# ad2_1.net
KiCad netlist of a schematic drawn in Altium Designer
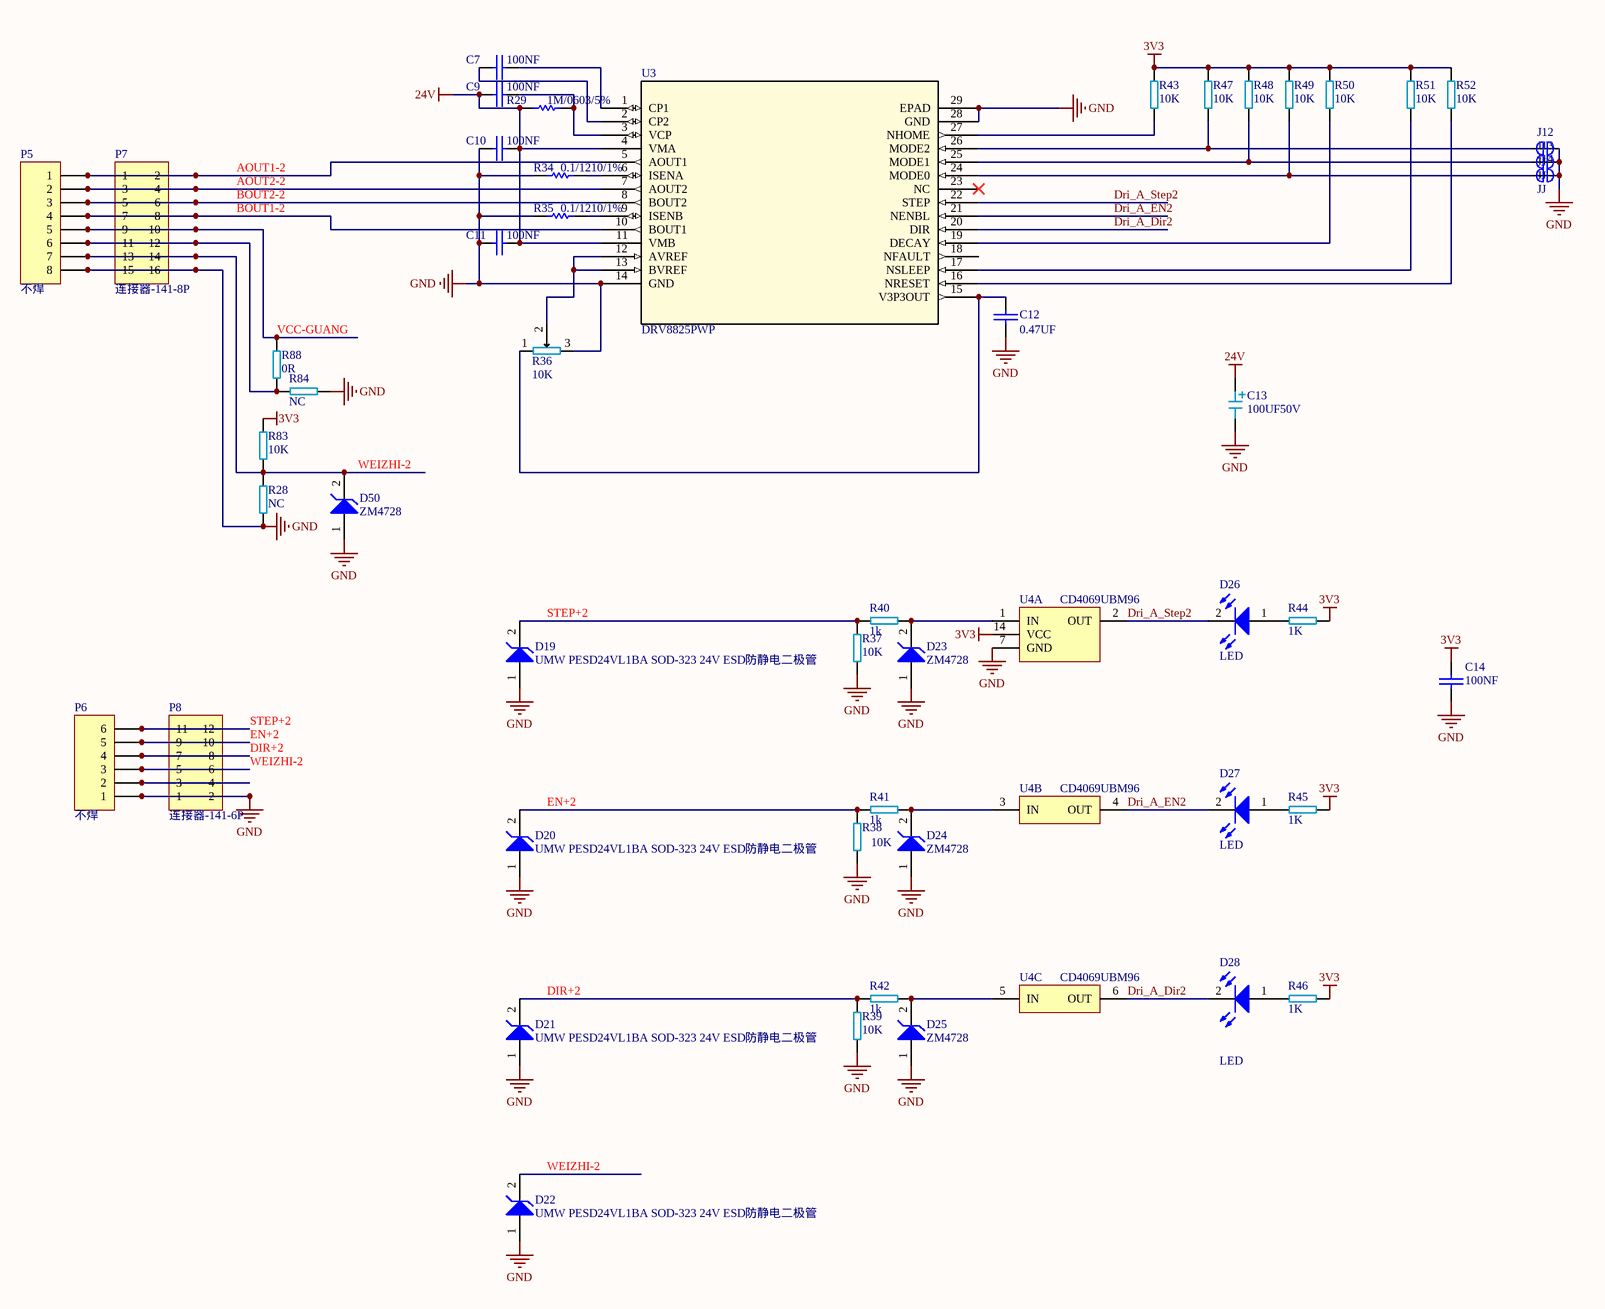
[diagram p0: ad2_1.schdoc]

(export (version "E")
  (design (tool "Eeschema 10.0.6"))
  (components
    (comp (ref "C7")
      (value "100NF")
      (footprint "C0603")
      (description "Capacitor")
      (libsource (lib "Miscellaneous Devices") (part "CAP"))
    )
    (comp (ref "C9")
      (value "100NF")
      (footprint "C0603")
      (description "Capacitor")
      (libsource (lib "Miscellaneous Devices") (part "CAP"))
    )
    (comp (ref "C10")
      (value "100NF")
      (footprint "C0603")
      (description "Capacitor")
      (libsource (lib "Miscellaneous Devices") (part "CAP"))
    )
    (comp (ref "C11")
      (value "100NF")
      (footprint "C0603")
      (description "Capacitor")
      (libsource (lib "Miscellaneous Devices") (part "CAP"))
    )
    (comp (ref "C12")
      (value "0.47UF")
      (footprint "C0603")
      (description "Capacitor")
      (libsource (lib "Miscellaneous Devices") (part "CAP"))
    )
    (comp (ref "C13")
      (value "100UF50V")
      (footprint "CE8")
      (description "铝电解电容")
      (libsource (lib "base") (part "C+"))
    )
    (comp (ref "C14")
      (value "100NF")
      (footprint "C0603")
      (description "Capacitor")
      (libsource (lib "Miscellaneous Devices") (part "CAP"))
    )
    (comp (ref "D19")
      (value "UMW PESD24VL1BA SOD-323 24V ESD防静电二极管")
      (footprint "SOD323")
      (description "稳压管")
      (fields (field (name "PUBLISHER") "Altium Limited"))
      (libsource (lib "base") (part "TVS-SMA"))
    )
    (comp (ref "D20")
      (value "UMW PESD24VL1BA SOD-323 24V ESD防静电二极管")
      (footprint "SOD323")
      (description "稳压管")
      (fields (field (name "PUBLISHER") "Altium Limited"))
      (libsource (lib "base") (part "TVS-SMA"))
    )
    (comp (ref "D21")
      (value "UMW PESD24VL1BA SOD-323 24V ESD防静电二极管")
      (footprint "SOD323")
      (description "稳压管")
      (fields (field (name "PUBLISHER") "Altium Limited"))
      (libsource (lib "base") (part "TVS-SMA"))
    )
    (comp (ref "D22")
      (value "UMW PESD24VL1BA SOD-323 24V ESD防静电二极管")
      (footprint "SOD323")
      (description "稳压管")
      (fields (field (name "PUBLISHER") "Altium Limited"))
      (libsource (lib "base") (part "TVS-SMA"))
    )
    (comp (ref "D23")
      (value "ZM4728")
      (footprint "D1206")
      (description "稳压管")
      (fields (field (name "PUBLISHER") "Altium Limited"))
      (libsource (lib "base") (part "TVS-SMA"))
    )
    (comp (ref "D24")
      (value "ZM4728")
      (footprint "D1206")
      (description "稳压管")
      (fields (field (name "PUBLISHER") "Altium Limited"))
      (libsource (lib "base") (part "TVS-SMA"))
    )
    (comp (ref "D25")
      (value "ZM4728")
      (footprint "D1206")
      (description "稳压管")
      (fields (field (name "PUBLISHER") "Altium Limited"))
      (libsource (lib "base") (part "TVS-SMA"))
    )
    (comp (ref "D26")
      (value "LED")
      (footprint "LED0603")
      (description "LED0603")
      (fields (field (name "PUBLISHER") "Altium Limited"))
      (libsource (lib "base") (part "LED0603"))
    )
    (comp (ref "D27")
      (value "LED")
      (footprint "LED0603")
      (description "LED0603")
      (fields (field (name "PUBLISHER") "Altium Limited"))
      (libsource (lib "base") (part "LED0603"))
    )
    (comp (ref "D28")
      (value "LED")
      (footprint "LED0603")
      (description "LED0603")
      (fields (field (name "PUBLISHER") "Altium Limited"))
      (libsource (lib "base") (part "LED0603"))
    )
    (comp (ref "D50")
      (value "ZM4728")
      (footprint "D1206")
      (description "稳压管")
      (fields (field (name "PUBLISHER") "Altium Limited"))
      (libsource (lib "base") (part "TVS-SMA"))
    )
    (comp (ref "J12")
      (value "JJ")
      (footprint "TIAOXIAN-PAN")
      (description "跳线")
      (libsource (lib "base") (part "JJ"))
    )
    (comp (ref "J13")
      (value "JJ")
      (footprint "TIAOXIAN-PAN")
      (description "跳线")
      (libsource (lib "base") (part "JJ"))
    )
    (comp (ref "J14")
      (value "JJ")
      (footprint "TIAOXIAN-PAN")
      (description "跳线")
      (libsource (lib "base") (part "JJ"))
    )
    (comp (ref "P5")
      (value "不焊")
      (footprint "SIP8")
      (description "连接器")
      (fields (field (name "PUBLISHER") "Altium Limited"))
      (libsource (lib "base") (part "SIP8"))
    )
    (comp (ref "P6")
      (value "不焊")
      (footprint "SIP6")
      (description "连接器")
      (fields (field (name "PUBLISHER") "Altium Limited"))
      (libsource (lib "base") (part "SIP6"))
    )
    (comp (ref "P7")
      (value "连接器-141-8P")
      (footprint "141V-8P")
      (description "连接器")
      (fields (field (name "PUBLISHER") "Altium Limited"))
      (libsource (lib "base") (part "DIC16"))
    )
    (comp (ref "P8")
      (value "连接器-141-6P")
      (footprint "141V-6P")
      (description "连接器")
      (fields (field (name "PUBLISHER") "Altium Limited"))
      (libsource (lib "base") (part "DIC12"))
    )
    (comp (ref "R28")
      (value "NC")
      (footprint "R0603")
      (description "贴片电阻")
      (libsource (lib "base") (part "R-0603"))
    )
    (comp (ref "R29")
      (value "1M/0603/5%")
      (footprint "R0603")
      (description "Resistor")
      (fields (field (name "PUBLISHER") "Altium Limited"))
      (libsource (lib "Miscellaneous Devices") (part "Res1"))
    )
    (comp (ref "R34")
      (value "0.1/1210/1%")
      (footprint "R1210")
      (description "Resistor")
      (fields (field (name "PUBLISHER") "Altium Limited"))
      (libsource (lib "Miscellaneous Devices") (part "Res1"))
    )
    (comp (ref "R35")
      (value "0.1/1210/1%")
      (footprint "R1210")
      (description "Resistor")
      (fields (field (name "PUBLISHER") "Altium Limited"))
      (libsource (lib "Miscellaneous Devices") (part "Res1"))
    )
    (comp (ref "R36")
      (value "10K")
      (footprint "RR-MINI-SMD")
      (description "电位器")
      (libsource (lib "base") (part "RR"))
    )
    (comp (ref "R37")
      (value "10K")
      (footprint "R0603")
      (description "贴片电阻")
      (libsource (lib "base") (part "R-0603"))
    )
    (comp (ref "R38")
      (value "10K")
      (footprint "R0603")
      (description "贴片电阻")
      (libsource (lib "base") (part "R-0603"))
    )
    (comp (ref "R39")
      (value "10K")
      (footprint "R0603")
      (description "贴片电阻")
      (libsource (lib "base") (part "R-0603"))
    )
    (comp (ref "R40")
      (value "1k")
      (footprint "R0603")
      (description "贴片电阻")
      (libsource (lib "base") (part "R-0603"))
    )
    (comp (ref "R41")
      (value "1k")
      (footprint "R0603")
      (description "贴片电阻")
      (libsource (lib "base") (part "R-0603"))
    )
    (comp (ref "R42")
      (value "1k")
      (footprint "R0603")
      (description "贴片电阻")
      (libsource (lib "base") (part "R-0603"))
    )
    (comp (ref "R43")
      (value "10K")
      (footprint "R0603")
      (description "贴片电阻")
      (libsource (lib "base") (part "R-0603"))
    )
    (comp (ref "R44")
      (value "1K")
      (footprint "R0603")
      (description "贴片电阻")
      (libsource (lib "base") (part "R-0603"))
    )
    (comp (ref "R45")
      (value "1K")
      (footprint "R0603")
      (description "贴片电阻")
      (libsource (lib "base") (part "R-0603"))
    )
    (comp (ref "R46")
      (value "1K")
      (footprint "R0603")
      (description "贴片电阻")
      (libsource (lib "base") (part "R-0603"))
    )
    (comp (ref "R47")
      (value "10K")
      (footprint "R0603")
      (description "贴片电阻")
      (libsource (lib "base") (part "R-0603"))
    )
    (comp (ref "R48")
      (value "10K")
      (footprint "R0603")
      (description "贴片电阻")
      (libsource (lib "base") (part "R-0603"))
    )
    (comp (ref "R49")
      (value "10K")
      (footprint "R0603")
      (description "贴片电阻")
      (libsource (lib "base") (part "R-0603"))
    )
    (comp (ref "R50")
      (value "10K")
      (footprint "R0603")
      (description "贴片电阻")
      (libsource (lib "base") (part "R-0603"))
    )
    (comp (ref "R51")
      (value "10K")
      (footprint "R0603")
      (description "贴片电阻")
      (libsource (lib "base") (part "R-0603"))
    )
    (comp (ref "R52")
      (value "10K")
      (footprint "R0603")
      (description "贴片电阻")
      (libsource (lib "base") (part "R-0603"))
    )
    (comp (ref "R83")
      (value "10K")
      (footprint "R0603")
      (description "贴片电阻")
      (libsource (lib "base") (part "R-0603"))
    )
    (comp (ref "R84")
      (value "NC")
      (footprint "R0603")
      (description "贴片电阻")
      (libsource (lib "base") (part "R-0603"))
    )
    (comp (ref "R88")
      (value "0R")
      (footprint "R0603")
      (description "贴片电阻")
      (libsource (lib "base") (part "R-0603"))
    )
    (comp (ref "U3")
      (value "DRV8825PWP")
      (footprint "HTSSOP28")
      (description "芯片")
      (libsource (lib "User") (part "DRV8825PWP"))
    )
    (comp (ref "U4")
      (value "CD4069UBM96")
      (footprint "SO14")
      (description "芯片")
      (libsource (lib "Chip") (part "CD4069"))
    )
  )
  (nets
    (net (code "1") (name "/AOUT1-2") (class "Default")
      (node (ref "P5") (pin "1") (pinfunction "1_1") (pintype "passive"))
      (node (ref "P7") (pin "1") (pinfunction "1_1") (pintype "passive"))
      (node (ref "P7") (pin "2") (pinfunction "2_2") (pintype "passive"))
      (node (ref "U3") (pin "5") (pinfunction "AOUT1_5") (pintype "output"))
    )
    (net (code "2") (name "/AOUT2-2") (class "Default")
      (node (ref "P5") (pin "2") (pinfunction "2_2") (pintype "passive"))
      (node (ref "P7") (pin "3") (pinfunction "3_3") (pintype "passive"))
      (node (ref "P7") (pin "4") (pinfunction "4_4") (pintype "passive"))
      (node (ref "U3") (pin "7") (pinfunction "AOUT2_7") (pintype "output"))
    )
    (net (code "3") (name "/BOUT1-2") (class "Default")
      (node (ref "P5") (pin "4") (pinfunction "4_4") (pintype "passive"))
      (node (ref "P7") (pin "7") (pinfunction "7_7") (pintype "passive"))
      (node (ref "P7") (pin "8") (pinfunction "8_8") (pintype "passive"))
      (node (ref "U3") (pin "10") (pinfunction "BOUT1_10") (pintype "output"))
    )
    (net (code "4") (name "/BOUT2-2") (class "Default")
      (node (ref "P5") (pin "3") (pinfunction "3_3") (pintype "passive"))
      (node (ref "P7") (pin "5") (pinfunction "5_5") (pintype "passive"))
      (node (ref "P7") (pin "6") (pinfunction "6_6") (pintype "passive"))
      (node (ref "U3") (pin "8") (pinfunction "BOUT2_8") (pintype "output"))
    )
    (net (code "5") (name "/DIR+2") (class "Default")
      (node (ref "D21") (pin "2") (pinfunction "2_2") (pintype "passive"))
      (node (ref "P6") (pin "4") (pinfunction "4_4") (pintype "passive"))
      (node (ref "P8") (pin "7") (pinfunction "7_7") (pintype "passive"))
      (node (ref "P8") (pin "8") (pinfunction "8_8") (pintype "passive"))
      (node (ref "R39") (pin "2") (pinfunction "2_2") (pintype "passive"))
      (node (ref "R42") (pin "2") (pinfunction "2_2") (pintype "passive"))
    )
    (net (code "6") (name "/Dri_A_Dir2") (class "Default")
      (node (ref "D28") (pin "2") (pinfunction "K_2") (pintype "passive"))
      (node (ref "U3") (pin "20") (pinfunction "DIR_20") (pintype "input"))
      (node (ref "U4") (pin "6") (pinfunction "OUT_6") (pintype "passive"))
    )
    (net (code "7") (name "/Dri_A_EN2") (class "Default")
      (node (ref "D27") (pin "2") (pinfunction "K_2") (pintype "passive"))
      (node (ref "U3") (pin "21") (pinfunction "NENBL_21") (pintype "input"))
      (node (ref "U4") (pin "4") (pinfunction "OUT_4") (pintype "passive"))
    )
    (net (code "8") (name "/Dri_A_Step2") (class "Default")
      (node (ref "D26") (pin "2") (pinfunction "K_2") (pintype "passive"))
      (node (ref "U3") (pin "22") (pinfunction "STEP_22") (pintype "input"))
      (node (ref "U4") (pin "2") (pinfunction "OUT_2") (pintype "passive"))
    )
    (net (code "9") (name "/EN+2") (class "Default")
      (node (ref "D20") (pin "2") (pinfunction "2_2") (pintype "passive"))
      (node (ref "P6") (pin "5") (pinfunction "5_5") (pintype "passive"))
      (node (ref "P8") (pin "10") (pinfunction "10_10") (pintype "passive"))
      (node (ref "P8") (pin "9") (pinfunction "9_9") (pintype "passive"))
      (node (ref "R38") (pin "2") (pinfunction "2_2") (pintype "passive"))
      (node (ref "R41") (pin "2") (pinfunction "2_2") (pintype "passive"))
    )
    (net (code "10") (name "/STEP+2") (class "Default")
      (node (ref "D19") (pin "2") (pinfunction "2_2") (pintype "passive"))
      (node (ref "P6") (pin "6") (pinfunction "6_6") (pintype "passive"))
      (node (ref "P8") (pin "11") (pinfunction "11_11") (pintype "passive"))
      (node (ref "P8") (pin "12") (pinfunction "12_12") (pintype "passive"))
      (node (ref "R37") (pin "2") (pinfunction "2_2") (pintype "passive"))
      (node (ref "R40") (pin "2") (pinfunction "2_2") (pintype "passive"))
    )
    (net (code "11") (name "/VCC-GUANG") (class "Default")
      (node (ref "P5") (pin "5") (pinfunction "5_5") (pintype "passive"))
      (node (ref "P7") (pin "10") (pinfunction "10_10") (pintype "passive"))
      (node (ref "P7") (pin "9") (pinfunction "9_9") (pintype "passive"))
      (node (ref "R88") (pin "2") (pinfunction "2_2") (pintype "passive"))
    )
    (net (code "12") (name "/WEIZHI-2") (class "Default")
      (node (ref "D22") (pin "2") (pinfunction "2_2") (pintype "passive"))
      (node (ref "D50") (pin "2") (pinfunction "2_2") (pintype "passive"))
      (node (ref "P5") (pin "7") (pinfunction "7_7") (pintype "passive"))
      (node (ref "P6") (pin "3") (pinfunction "3_3") (pintype "passive"))
      (node (ref "P7") (pin "13") (pinfunction "13_13") (pintype "passive"))
      (node (ref "P7") (pin "14") (pinfunction "14_14") (pintype "passive"))
      (node (ref "P8") (pin "5") (pinfunction "5_5") (pintype "passive"))
      (node (ref "P8") (pin "6") (pinfunction "6_6") (pintype "passive"))
      (node (ref "R28") (pin "2") (pinfunction "2_2") (pintype "passive"))
      (node (ref "R83") (pin "1") (pinfunction "1_1") (pintype "passive"))
    )
    (net (code "13") (name "3V3") (class "Default")
      (node (ref "C14") (pin "2") (pinfunction "2_2") (pintype "passive"))
      (node (ref "R43") (pin "2") (pinfunction "2_2") (pintype "passive"))
      (node (ref "R44") (pin "2") (pinfunction "2_2") (pintype "passive"))
      (node (ref "R45") (pin "2") (pinfunction "2_2") (pintype "passive"))
      (node (ref "R46") (pin "2") (pinfunction "2_2") (pintype "passive"))
      (node (ref "R47") (pin "2") (pinfunction "2_2") (pintype "passive"))
      (node (ref "R48") (pin "2") (pinfunction "2_2") (pintype "passive"))
      (node (ref "R49") (pin "2") (pinfunction "2_2") (pintype "passive"))
      (node (ref "R50") (pin "2") (pinfunction "2_2") (pintype "passive"))
      (node (ref "R51") (pin "2") (pinfunction "2_2") (pintype "passive"))
      (node (ref "R52") (pin "2") (pinfunction "2_2") (pintype "passive"))
      (node (ref "R83") (pin "2") (pinfunction "2_2") (pintype "passive"))
      (node (ref "U4") (pin "14") (pinfunction "VCC_14") (pintype "passive"))
    )
    (net (code "14") (name "24V") (class "Default")
      (node (ref "C10") (pin "2") (pinfunction "2_2") (pintype "passive"))
      (node (ref "C11") (pin "2") (pinfunction "2_2") (pintype "passive"))
      (node (ref "C13") (pin "1") (pinfunction "1_1") (pintype "passive"))
      (node (ref "C9") (pin "1") (pinfunction "1_1") (pintype "passive"))
      (node (ref "R29") (pin "2") (pinfunction "2_2") (pintype "passive"))
      (node (ref "U3") (pin "11") (pinfunction "VMB_11") (pintype "power_in"))
      (node (ref "U3") (pin "4") (pinfunction "VMA_4") (pintype "power_in"))
    )
    (net (code "15") (name "GND") (class "Default")
      (node (ref "C10") (pin "1") (pinfunction "1_1") (pintype "passive"))
      (node (ref "C11") (pin "1") (pinfunction "1_1") (pintype "passive"))
      (node (ref "C12") (pin "1") (pinfunction "1_1") (pintype "passive"))
      (node (ref "C13") (pin "2") (pinfunction "2_2") (pintype "passive"))
      (node (ref "C14") (pin "1") (pinfunction "1_1") (pintype "passive"))
      (node (ref "D19") (pin "1") (pinfunction "1_1") (pintype "passive"))
      (node (ref "D20") (pin "1") (pinfunction "1_1") (pintype "passive"))
      (node (ref "D21") (pin "1") (pinfunction "1_1") (pintype "passive"))
      (node (ref "D22") (pin "1") (pinfunction "1_1") (pintype "passive"))
      (node (ref "D23") (pin "1") (pinfunction "1_1") (pintype "passive"))
      (node (ref "D24") (pin "1") (pinfunction "1_1") (pintype "passive"))
      (node (ref "D25") (pin "1") (pinfunction "1_1") (pintype "passive"))
      (node (ref "D50") (pin "1") (pinfunction "1_1") (pintype "passive"))
      (node (ref "J12") (pin "2") (pinfunction "2_2") (pintype "passive"))
      (node (ref "J13") (pin "2") (pinfunction "2_2") (pintype "passive"))
      (node (ref "J14") (pin "2") (pinfunction "2_2") (pintype "passive"))
      (node (ref "P5") (pin "8") (pinfunction "8_8") (pintype "passive"))
      (node (ref "P6") (pin "1") (pinfunction "1_1") (pintype "passive"))
      (node (ref "P7") (pin "15") (pinfunction "15_15") (pintype "passive"))
      (node (ref "P7") (pin "16") (pinfunction "16_16") (pintype "passive"))
      (node (ref "P8") (pin "1") (pinfunction "1_1") (pintype "passive"))
      (node (ref "P8") (pin "2") (pinfunction "2_2") (pintype "passive"))
      (node (ref "R28") (pin "1") (pinfunction "1_1") (pintype "passive"))
      (node (ref "R34") (pin "2") (pinfunction "2_2") (pintype "passive"))
      (node (ref "R35") (pin "2") (pinfunction "2_2") (pintype "passive"))
      (node (ref "R36") (pin "3") (pinfunction "3_3") (pintype "passive"))
      (node (ref "R37") (pin "1") (pinfunction "1_1") (pintype "passive"))
      (node (ref "R38") (pin "1") (pinfunction "1_1") (pintype "passive"))
      (node (ref "R39") (pin "1") (pinfunction "1_1") (pintype "passive"))
      (node (ref "R84") (pin "1") (pinfunction "1_1") (pintype "passive"))
      (node (ref "U3") (pin "14") (pinfunction "GND_14") (pintype "power_in"))
      (node (ref "U3") (pin "28") (pinfunction "GND_28") (pintype "power_in"))
      (node (ref "U3") (pin "29") (pinfunction "EPAD_29") (pintype "passive"))
      (node (ref "U4") (pin "7") (pinfunction "GND_7") (pintype "passive"))
    )
    (net (code "16") (name "Net-(D26-A)") (class "Default")
      (node (ref "D26") (pin "1") (pinfunction "A_1") (pintype "passive"))
      (node (ref "R44") (pin "1") (pinfunction "1_1") (pintype "passive"))
    )
    (net (code "17") (name "Net-(D27-A)") (class "Default")
      (node (ref "D27") (pin "1") (pinfunction "A_1") (pintype "passive"))
      (node (ref "R45") (pin "1") (pinfunction "1_1") (pintype "passive"))
    )
    (net (code "18") (name "Net-(D28-A)") (class "Default")
      (node (ref "D28") (pin "1") (pinfunction "A_1") (pintype "passive"))
      (node (ref "R46") (pin "1") (pinfunction "1_1") (pintype "passive"))
    )
    (net (code "19") (name "Net-(P5-Pad6)") (class "Default")
      (node (ref "P5") (pin "6") (pinfunction "6_6") (pintype "passive"))
      (node (ref "P7") (pin "11") (pinfunction "11_11") (pintype "passive"))
      (node (ref "P7") (pin "12") (pinfunction "12_12") (pintype "passive"))
      (node (ref "R84") (pin "2") (pinfunction "2_2") (pintype "passive"))
      (node (ref "R88") (pin "1") (pinfunction "1_1") (pintype "passive"))
    )
    (net (code "20") (name "Net-(P6-Pad2)") (class "Default")
      (node (ref "P6") (pin "2") (pinfunction "2_2") (pintype "passive"))
      (node (ref "P8") (pin "3") (pinfunction "3_3") (pintype "passive"))
      (node (ref "P8") (pin "4") (pinfunction "4_4") (pintype "passive"))
    )
    (net (code "21") (name "Net-(U3-AVREF)") (class "Default")
      (node (ref "R36") (pin "2") (pinfunction "2_2") (pintype "passive"))
      (node (ref "U3") (pin "12") (pinfunction "AVREF_12") (pintype "input"))
      (node (ref "U3") (pin "13") (pinfunction "BVREF_13") (pintype "input"))
    )
    (net (code "22") (name "Net-(U3-CP1)") (class "Default")
      (node (ref "C7") (pin "2") (pinfunction "2_2") (pintype "passive"))
      (node (ref "U3") (pin "1") (pinfunction "CP1_1") (pintype "bidirectional"))
    )
    (net (code "23") (name "Net-(U3-CP2)") (class "Default")
      (node (ref "C7") (pin "1") (pinfunction "1_1") (pintype "passive"))
      (node (ref "U3") (pin "2") (pinfunction "CP2_2") (pintype "bidirectional"))
    )
    (net (code "24") (name "Net-(U3-DECAY)") (class "Default")
      (node (ref "R50") (pin "1") (pinfunction "1_1") (pintype "passive"))
      (node (ref "U3") (pin "19") (pinfunction "DECAY_19") (pintype "input"))
    )
    (net (code "25") (name "Net-(U3-ISENA)") (class "Default")
      (node (ref "R34") (pin "1") (pinfunction "1_1") (pintype "passive"))
      (node (ref "U3") (pin "6") (pinfunction "ISENA_6") (pintype "bidirectional"))
    )
    (net (code "26") (name "Net-(U3-ISENB)") (class "Default")
      (node (ref "R35") (pin "1") (pinfunction "1_1") (pintype "passive"))
      (node (ref "U3") (pin "9") (pinfunction "ISENB_9") (pintype "bidirectional"))
    )
    (net (code "27") (name "Net-(U3-MODE0)") (class "Default")
      (node (ref "J14") (pin "1") (pinfunction "1_1") (pintype "passive"))
      (node (ref "R49") (pin "1") (pinfunction "1_1") (pintype "passive"))
      (node (ref "U3") (pin "24") (pinfunction "MODE0_24") (pintype "input"))
    )
    (net (code "28") (name "Net-(U3-MODE1)") (class "Default")
      (node (ref "J13") (pin "1") (pinfunction "1_1") (pintype "passive"))
      (node (ref "R48") (pin "1") (pinfunction "1_1") (pintype "passive"))
      (node (ref "U3") (pin "25") (pinfunction "MODE1_25") (pintype "input"))
    )
    (net (code "29") (name "Net-(U3-MODE2)") (class "Default")
      (node (ref "J12") (pin "1") (pinfunction "1_1") (pintype "passive"))
      (node (ref "R47") (pin "1") (pinfunction "1_1") (pintype "passive"))
      (node (ref "U3") (pin "26") (pinfunction "MODE2_26") (pintype "input"))
    )
    (net (code "30") (name "Net-(U3-NHOME)") (class "Default")
      (node (ref "R43") (pin "1") (pinfunction "1_1") (pintype "passive"))
      (node (ref "U3") (pin "27") (pinfunction "NHOME_27") (pintype "output"))
    )
    (net (code "31") (name "Net-(U3-NRESET)") (class "Default")
      (node (ref "R52") (pin "1") (pinfunction "1_1") (pintype "passive"))
      (node (ref "U3") (pin "16") (pinfunction "NRESET_16") (pintype "input"))
    )
    (net (code "32") (name "Net-(U3-NSLEEP)") (class "Default")
      (node (ref "R51") (pin "1") (pinfunction "1_1") (pintype "passive"))
      (node (ref "U3") (pin "17") (pinfunction "NSLEEP_17") (pintype "input"))
    )
    (net (code "33") (name "Net-(U3-V3P3OUT)") (class "Default")
      (node (ref "C12") (pin "2") (pinfunction "2_2") (pintype "passive"))
      (node (ref "R36") (pin "1") (pinfunction "1_1") (pintype "passive"))
      (node (ref "U3") (pin "15") (pinfunction "V3P3OUT_15") (pintype "output"))
    )
    (net (code "34") (name "Net-(U3-VCP)") (class "Default")
      (node (ref "C9") (pin "2") (pinfunction "2_2") (pintype "passive"))
      (node (ref "R29") (pin "1") (pinfunction "1_1") (pintype "passive"))
      (node (ref "U3") (pin "3") (pinfunction "VCP_3") (pintype "bidirectional"))
    )
    (net (code "35") (name "Net-(U4A-IN)") (class "Default")
      (node (ref "D23") (pin "2") (pinfunction "2_2") (pintype "passive"))
      (node (ref "R40") (pin "1") (pinfunction "1_1") (pintype "passive"))
      (node (ref "U4") (pin "1") (pinfunction "IN_1") (pintype "passive"))
    )
    (net (code "36") (name "Net-(U4B-IN)") (class "Default")
      (node (ref "D24") (pin "2") (pinfunction "2_2") (pintype "passive"))
      (node (ref "R41") (pin "1") (pinfunction "1_1") (pintype "passive"))
      (node (ref "U4") (pin "3") (pinfunction "IN_3") (pintype "passive"))
    )
    (net (code "37") (name "Net-(U4C-IN)") (class "Default")
      (node (ref "D25") (pin "2") (pinfunction "2_2") (pintype "passive"))
      (node (ref "R42") (pin "1") (pinfunction "1_1") (pintype "passive"))
      (node (ref "U4") (pin "5") (pinfunction "IN_5") (pintype "passive"))
    )
    (net (code "38") (name "unconnected-(U3-NC-Pad23)") (class "Default")
      (node (ref "U3") (pin "23") (pinfunction "NC_23") (pintype "passive+no_connect"))
    )
    (net (code "39") (name "unconnected-(U3-NFAULT-Pad18)") (class "Default")
      (node (ref "U3") (pin "18") (pinfunction "NFAULT_18") (pintype "output"))
    )
  )
)
